# X15-ESC-CONTROLLER_-_Copy.net
KiCad netlist of a schematic drawn in EAGLE
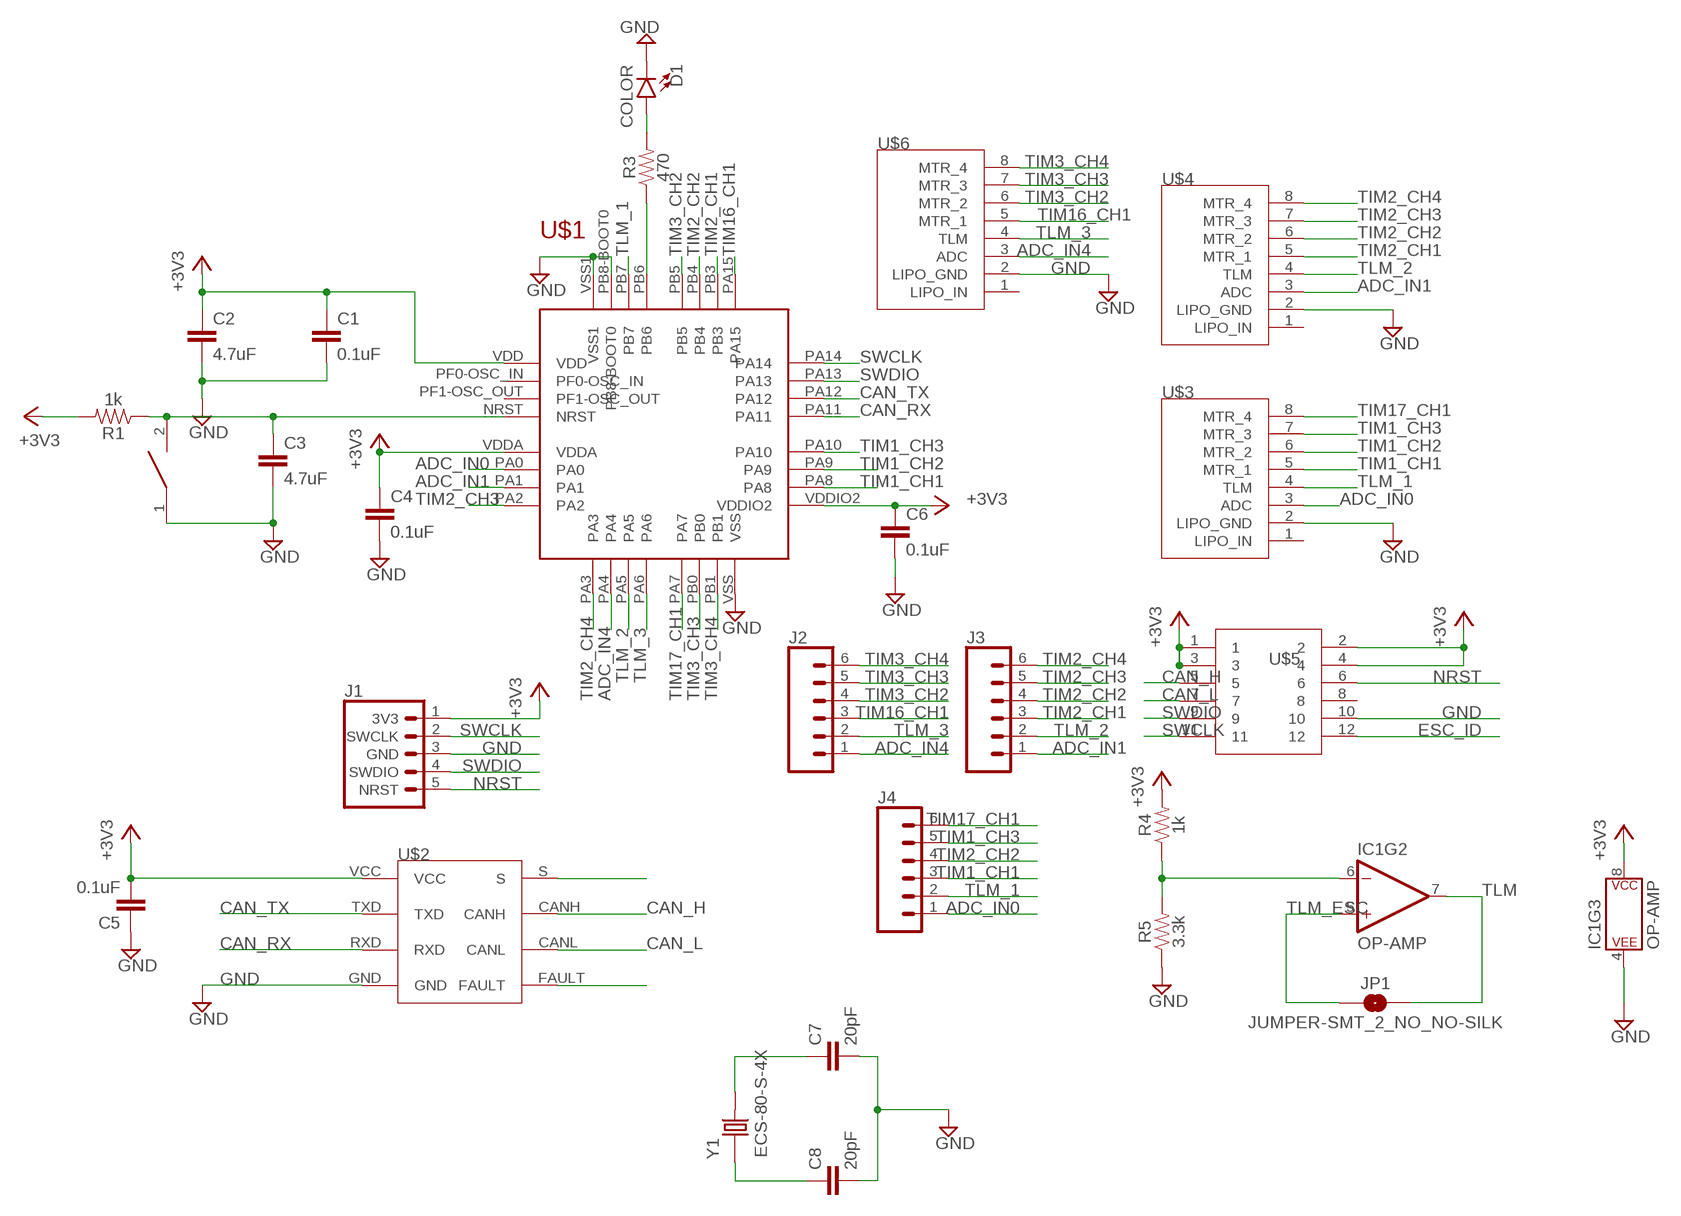
[diagram p0: schematic, sheet 1]

(export (version "E")
  (design (tool "Eeschema 10.0.6"))
  (components
    (comp (ref "C1")
      (value "0.1uF")
      (footprint "eagle-import:0603")
      (libsource (lib "eagle-import") (part "0.1UF-0603-25V-5%"))
    )
    (comp (ref "C2")
      (value "4.7uF")
      (footprint "eagle-import:0603")
      (libsource (lib "eagle-import") (part "4.7UF-0603-6.3V-(10%)"))
    )
    (comp (ref "C3")
      (value "4.7uF")
      (footprint "eagle-import:0603")
      (libsource (lib "eagle-import") (part "4.7UF-0603-6.3V-(10%)"))
    )
    (comp (ref "C4")
      (value "0.1uF")
      (footprint "eagle-import:0603")
      (libsource (lib "eagle-import") (part "0.1UF-0603-50V-10%-X7R-WE"))
    )
    (comp (ref "C5")
      (value "0.1uF")
      (footprint "eagle-import:0603")
      (libsource (lib "eagle-import") (part "0.1UF-0603-25V-(+80/-20%)"))
    )
    (comp (ref "C6")
      (value "0.1uF")
      (footprint "eagle-import:0603")
      (libsource (lib "eagle-import") (part "0.1UF-0603-25V-(+80/-20%)"))
    )
    (comp (ref "C7")
      (value "20pF")
      (footprint "eagle-import:0402-TIGHT")
      (libsource (lib "eagle-import") (part "20PF-0402T-50V-5%"))
    )
    (comp (ref "C8")
      (value "20pF")
      (footprint "eagle-import:0402-TIGHT")
      (libsource (lib "eagle-import") (part "20PF-0402T-50V-5%"))
    )
    (comp (ref "D1")
      (value "COLOR")
      (footprint "eagle-import:0805")
      (libsource (lib "eagle-import") (part "LED-0805"))
    )
    (comp (ref "IC1")
      (value "OP-AMP")
      (footprint "eagle-import:SO08")
      (libsource (lib "eagle-import") (part "OPAMP-DUALU"))
    )
    (comp (ref "J1")
      (value "3V3 -SWCLK-GND-SWDIO- NRST")
      (footprint "eagle-import:1X05")
      (libsource (lib "eagle-import") (part "SWD_CONN"))
    )
    (comp (ref "J2")
      (value "CONN_06NO_SILK_NO_POP")
      (footprint "eagle-import:1X06_NO_SILK")
      (libsource (lib "eagle-import") (part "CONN_06NO_SILK_NO_POP"))
    )
    (comp (ref "J3")
      (value "CONN_06NO_SILK_NO_POP")
      (footprint "eagle-import:1X06_NO_SILK")
      (libsource (lib "eagle-import") (part "CONN_06NO_SILK_NO_POP"))
    )
    (comp (ref "J4")
      (value "CONN_06NO_SILK_NO_POP")
      (footprint "eagle-import:1X06_NO_SILK")
      (libsource (lib "eagle-import") (part "CONN_06NO_SILK_NO_POP"))
    )
    (comp (ref "JP1")
      (value "JUMPER-SMT_2_NO_NO-SILK")
      (footprint "eagle-import:SMT-JUMPER_2_NO_NO-SILK")
      (libsource (lib "eagle-import") (part "JUMPER-SMT_2_NO_NO-SILK"))
    )
    (comp (ref "R1")
      (value "1k")
      (footprint "eagle-import:0603")
      (libsource (lib "eagle-import") (part "1KOHM-0603-1/10W-1%"))
    )
    (comp (ref "R3")
      (value "470")
      (footprint "eagle-import:0603")
      (libsource (lib "eagle-import") (part "10KOHM-0603-1/10W-1%"))
    )
    (comp (ref "R4")
      (value "1k")
      (footprint "eagle-import:0603")
      (libsource (lib "eagle-import") (part "1KOHM-0603-1/10W-1%"))
    )
    (comp (ref "R5")
      (value "3.3k")
      (footprint "eagle-import:0603")
      (libsource (lib "eagle-import") (part "1KOHM-0603-1/10W-1%"))
    )
    (comp (ref "U$1")
      (value "STM32F042K6T6")
      (footprint "eagle-import:STM32F042K6T6")
      (libsource (lib "eagle-import") (part "STM32F042K6T6"))
    )
    (comp (ref "U$2")
      (value "TCAN337D")
      (footprint "eagle-import:TCAN337D")
      (libsource (lib "eagle-import") (part "TCAN337D"))
    )
    (comp (ref "U$3")
      (value "JST_8_PIN")
      (footprint "eagle-import:JST_8_PIN")
      (libsource (lib "eagle-import") (part "JST_8_PIN"))
    )
    (comp (ref "U$4")
      (value "JST_8_PIN")
      (footprint "eagle-import:JST_8_PIN")
      (libsource (lib "eagle-import") (part "JST_8_PIN"))
    )
    (comp (ref "U$5")
      (value "BAKCPLANE_CONNECTOR")
      (footprint "eagle-import:BACKPLANE_CONNECTORS_BKP")
      (libsource (lib "eagle-import") (part "BAKCPLANE_CONNECTOR"))
    )
    (comp (ref "U$6")
      (value "JST_8_PIN")
      (footprint "eagle-import:JST_8_PIN")
      (libsource (lib "eagle-import") (part "JST_8_PIN"))
    )
    (comp (ref "U$7")
      (value "DISCRETECOMPONENTS_SWITCH")
      (footprint "eagle-import:DISCRETECOMPONENTS_SW_2512")
      (libsource (lib "eagle-import") (part "DISCRETECOMPONENTS_SWITCH"))
    )
    (comp (ref "Y1")
      (value "ECS-80-S-4X")
      (footprint "eagle-import:XTAL_ECS-80-S-4X")
      (fields (field (name "DIGI-KEY_PART_NUMBER") "X1057-ND") (field (name "MF") "ECS International"))
      (libsource (lib "eagle-import") (part "ECS-80-S-4X"))
    )
  )
  (nets
    (net (code "1") (name "+3V3") (class "Default")
      (node (ref "C1") (pin "1") (pinfunction "1_1") (pintype "passive"))
      (node (ref "C2") (pin "1") (pinfunction "1_1") (pintype "passive"))
      (node (ref "C4") (pin "1") (pinfunction "1_1") (pintype "passive"))
      (node (ref "C5") (pin "2") (pinfunction "2_2") (pintype "passive"))
      (node (ref "C6") (pin "1") (pinfunction "1_1") (pintype "passive"))
      (node (ref "IC1") (pin "8") (pinfunction "P$V+_8") (pintype "bidirectional"))
      (node (ref "J1") (pin "1") (pinfunction "3V3_1") (pintype "power_in"))
      (node (ref "R1") (pin "2") (pinfunction "2_2") (pintype "passive"))
      (node (ref "R4") (pin "2") (pinfunction "2_2") (pintype "passive"))
      (node (ref "U$1") (pin "VDD") (pinfunction "VDD_VDD") (pintype "bidirectional"))
      (node (ref "U$1") (pin "VDDA") (pinfunction "VDDA_VDDA") (pintype "bidirectional"))
      (node (ref "U$1") (pin "VDDIO2") (pinfunction "VDDIO2_VDDIO2") (pintype "bidirectional"))
      (node (ref "U$2") (pin "VCC") (pinfunction "VCC_VCC") (pintype "bidirectional"))
      (node (ref "U$5") (pin "1") (pinfunction "1_1") (pintype "bidirectional"))
      (node (ref "U$5") (pin "2") (pinfunction "2_2") (pintype "bidirectional"))
      (node (ref "U$5") (pin "3") (pinfunction "3_3") (pintype "bidirectional"))
      (node (ref "U$5") (pin "4") (pinfunction "4_4") (pintype "bidirectional"))
    )
    (net (code "2") (name "/ADC_IN0") (class "Default")
      (node (ref "J4") (pin "1") (pinfunction "1_1") (pintype "passive"))
      (node (ref "U$1") (pin "PA0") (pinfunction "PA0_PA0") (pintype "bidirectional"))
      (node (ref "U$3") (pin "3") (pinfunction "ADC_3") (pintype "bidirectional"))
    )
    (net (code "3") (name "/ADC_IN1") (class "Default")
      (node (ref "J3") (pin "1") (pinfunction "1_1") (pintype "passive"))
      (node (ref "U$1") (pin "PA1") (pinfunction "PA1_PA1") (pintype "bidirectional"))
      (node (ref "U$4") (pin "3") (pinfunction "ADC_3") (pintype "bidirectional"))
    )
    (net (code "4") (name "/ADC_IN4") (class "Default")
      (node (ref "J2") (pin "1") (pinfunction "1_1") (pintype "passive"))
      (node (ref "U$1") (pin "PA4") (pinfunction "PA4_PA4") (pintype "bidirectional"))
      (node (ref "U$6") (pin "3") (pinfunction "ADC_3") (pintype "bidirectional"))
    )
    (net (code "5") (name "/CAN_H") (class "Default")
      (node (ref "U$2") (pin "CANH") (pinfunction "CANH_CANH") (pintype "bidirectional"))
      (node (ref "U$5") (pin "5") (pinfunction "5_5") (pintype "bidirectional"))
    )
    (net (code "6") (name "/CAN_L") (class "Default")
      (node (ref "U$2") (pin "CANL") (pinfunction "CANL_CANL") (pintype "bidirectional"))
      (node (ref "U$5") (pin "7") (pinfunction "7_7") (pintype "bidirectional"))
    )
    (net (code "7") (name "/CAN_RX") (class "Default")
      (node (ref "U$1") (pin "PA11") (pinfunction "PA11_PA11") (pintype "bidirectional"))
      (node (ref "U$2") (pin "RXD") (pinfunction "RXD_RXD") (pintype "bidirectional"))
    )
    (net (code "8") (name "/CAN_TX") (class "Default")
      (node (ref "U$1") (pin "PA12") (pinfunction "PA12_PA12") (pintype "bidirectional"))
      (node (ref "U$2") (pin "TXD") (pinfunction "TXD_TXD") (pintype "bidirectional"))
    )
    (net (code "9") (name "/ESC_ID") (class "Default")
      (node (ref "U$5") (pin "12") (pinfunction "12_12") (pintype "bidirectional"))
    )
    (net (code "10") (name "/NRST") (class "Default")
      (node (ref "J1") (pin "5") (pinfunction "NRST_5") (pintype "open_collector"))
      (node (ref "U$5") (pin "6") (pinfunction "6_6") (pintype "bidirectional"))
    )
    (net (code "11") (name "/SWCLK") (class "Default")
      (node (ref "J1") (pin "2") (pinfunction "SWCLK_2") (pintype "input"))
      (node (ref "U$1") (pin "PA14") (pinfunction "PA14_PA14") (pintype "bidirectional"))
      (node (ref "U$5") (pin "11") (pinfunction "11_11") (pintype "bidirectional"))
    )
    (net (code "12") (name "/SWDIO") (class "Default")
      (node (ref "J1") (pin "4") (pinfunction "SWDIO_4") (pintype "bidirectional"))
      (node (ref "U$1") (pin "PA13") (pinfunction "PA13_PA13") (pintype "bidirectional"))
      (node (ref "U$5") (pin "9") (pinfunction "9_9") (pintype "bidirectional"))
    )
    (net (code "13") (name "/TIM1_CH1") (class "Default")
      (node (ref "J4") (pin "3") (pinfunction "3_3") (pintype "passive"))
      (node (ref "U$1") (pin "PA8") (pinfunction "PA8_PA8") (pintype "bidirectional"))
      (node (ref "U$3") (pin "5") (pinfunction "MTR_1_5") (pintype "bidirectional"))
    )
    (net (code "14") (name "/TIM1_CH2") (class "Default")
      (node (ref "U$1") (pin "PA9") (pinfunction "PA9_PA9") (pintype "bidirectional"))
      (node (ref "U$3") (pin "6") (pinfunction "MTR_2_6") (pintype "bidirectional"))
    )
    (net (code "15") (name "/TIM1_CH3") (class "Default")
      (node (ref "J4") (pin "5") (pinfunction "5_5") (pintype "passive"))
      (node (ref "U$1") (pin "PA10") (pinfunction "PA10_PA10") (pintype "bidirectional"))
      (node (ref "U$3") (pin "7") (pinfunction "MTR_3_7") (pintype "bidirectional"))
    )
    (net (code "16") (name "/TIM2_CH1") (class "Default")
      (node (ref "J3") (pin "3") (pinfunction "3_3") (pintype "passive"))
      (node (ref "U$1") (pin "PB3") (pinfunction "PB3_PB3") (pintype "bidirectional"))
      (node (ref "U$4") (pin "5") (pinfunction "MTR_1_5") (pintype "bidirectional"))
    )
    (net (code "17") (name "/TIM2_CH2") (class "Default")
      (node (ref "J3") (pin "4") (pinfunction "4_4") (pintype "passive"))
      (node (ref "J4") (pin "4") (pinfunction "4_4") (pintype "passive"))
      (node (ref "U$1") (pin "PB4") (pinfunction "PB4_PB4") (pintype "bidirectional"))
      (node (ref "U$4") (pin "6") (pinfunction "MTR_2_6") (pintype "bidirectional"))
    )
    (net (code "18") (name "/TIM2_CH3") (class "Default")
      (node (ref "J3") (pin "5") (pinfunction "5_5") (pintype "passive"))
      (node (ref "U$1") (pin "PA2") (pinfunction "PA2_PA2") (pintype "bidirectional"))
      (node (ref "U$4") (pin "7") (pinfunction "MTR_3_7") (pintype "bidirectional"))
    )
    (net (code "19") (name "/TIM2_CH4") (class "Default")
      (node (ref "J3") (pin "6") (pinfunction "6_6") (pintype "passive"))
      (node (ref "U$1") (pin "PA3") (pinfunction "PA3_PA3") (pintype "bidirectional"))
      (node (ref "U$4") (pin "8") (pinfunction "MTR_4_8") (pintype "bidirectional"))
    )
    (net (code "20") (name "/TIM3_CH2") (class "Default")
      (node (ref "J2") (pin "4") (pinfunction "4_4") (pintype "passive"))
      (node (ref "U$1") (pin "PB5") (pinfunction "PB5_PB5") (pintype "bidirectional"))
      (node (ref "U$6") (pin "6") (pinfunction "MTR_2_6") (pintype "bidirectional"))
    )
    (net (code "21") (name "/TIM3_CH3") (class "Default")
      (node (ref "J2") (pin "5") (pinfunction "5_5") (pintype "passive"))
      (node (ref "U$1") (pin "PB0") (pinfunction "PB0_PB0") (pintype "bidirectional"))
      (node (ref "U$6") (pin "7") (pinfunction "MTR_3_7") (pintype "bidirectional"))
    )
    (net (code "22") (name "/TIM3_CH4") (class "Default")
      (node (ref "J2") (pin "6") (pinfunction "6_6") (pintype "passive"))
      (node (ref "U$1") (pin "PB1") (pinfunction "PB1_PB1") (pintype "bidirectional"))
      (node (ref "U$6") (pin "8") (pinfunction "MTR_4_8") (pintype "bidirectional"))
    )
    (net (code "23") (name "/TIM16_CH1") (class "Default")
      (node (ref "J2") (pin "3") (pinfunction "3_3") (pintype "passive"))
      (node (ref "U$1") (pin "PA15") (pinfunction "PA15_PA15") (pintype "bidirectional"))
      (node (ref "U$6") (pin "5") (pinfunction "MTR_1_5") (pintype "bidirectional"))
    )
    (net (code "24") (name "/TIM17_CH1") (class "Default")
      (node (ref "J4") (pin "6") (pinfunction "6_6") (pintype "passive"))
      (node (ref "U$1") (pin "PA7") (pinfunction "PA7_PA7") (pintype "bidirectional"))
      (node (ref "U$3") (pin "8") (pinfunction "MTR_4_8") (pintype "bidirectional"))
    )
    (net (code "25") (name "/TLM") (class "Default")
      (node (ref "IC1") (pin "7") (pinfunction "OUT_7") (pintype "output"))
      (node (ref "JP1") (pin "2") (pinfunction "2_2") (pintype "passive"))
    )
    (net (code "26") (name "/TLM_1") (class "Default")
      (node (ref "J4") (pin "2") (pinfunction "2_2") (pintype "passive"))
      (node (ref "U$1") (pin "PB7") (pinfunction "PB7_PB7") (pintype "bidirectional"))
      (node (ref "U$3") (pin "4") (pinfunction "TLM_4") (pintype "bidirectional"))
    )
    (net (code "27") (name "/TLM_2") (class "Default")
      (node (ref "J3") (pin "2") (pinfunction "2_2") (pintype "passive"))
      (node (ref "U$1") (pin "PA5") (pinfunction "PA5_PA5") (pintype "bidirectional"))
      (node (ref "U$4") (pin "4") (pinfunction "TLM_4") (pintype "bidirectional"))
    )
    (net (code "28") (name "/TLM_3") (class "Default")
      (node (ref "J2") (pin "2") (pinfunction "2_2") (pintype "passive"))
      (node (ref "U$1") (pin "PA6") (pinfunction "PA6_PA6") (pintype "bidirectional"))
      (node (ref "U$6") (pin "4") (pinfunction "TLM_4") (pintype "bidirectional"))
    )
    (net (code "29") (name "/TLM_ESC") (class "Default")
      (node (ref "IC1") (pin "5") (pinfunction "+IN_5") (pintype "input"))
      (node (ref "JP1") (pin "1") (pinfunction "1_1") (pintype "passive"))
    )
    (net (code "30") (name "GND") (class "Default")
      (node (ref "C1") (pin "2") (pinfunction "2_2") (pintype "passive"))
      (node (ref "C2") (pin "2") (pinfunction "2_2") (pintype "passive"))
      (node (ref "C3") (pin "2") (pinfunction "2_2") (pintype "passive"))
      (node (ref "C4") (pin "2") (pinfunction "2_2") (pintype "passive"))
      (node (ref "C5") (pin "1") (pinfunction "1_1") (pintype "passive"))
      (node (ref "C6") (pin "2") (pinfunction "2_2") (pintype "passive"))
      (node (ref "C7") (pin "2") (pinfunction "2_2") (pintype "passive"))
      (node (ref "C8") (pin "2") (pinfunction "2_2") (pintype "passive"))
      (node (ref "D1") (pin "C") (pinfunction "C_C") (pintype "passive"))
      (node (ref "IC1") (pin "4") (pinfunction "P$V-_4") (pintype "bidirectional"))
      (node (ref "J1") (pin "3") (pinfunction "GND_3") (pintype "power_in"))
      (node (ref "R5") (pin "1") (pinfunction "1_1") (pintype "passive"))
      (node (ref "U$1") (pin "PB8-BOOT0") (pinfunction "PB8-BOOT0_PB8-BOOT0") (pintype "bidirectional"))
      (node (ref "U$1") (pin "VSS") (pinfunction "VSS_VSS") (pintype "bidirectional"))
      (node (ref "U$1") (pin "VSS1") (pinfunction "VSS1_VSS1") (pintype "bidirectional"))
      (node (ref "U$2") (pin "GND") (pinfunction "GND_GND") (pintype "bidirectional"))
      (node (ref "U$3") (pin "2") (pinfunction "LIPO_GND_2") (pintype "bidirectional"))
      (node (ref "U$4") (pin "2") (pinfunction "LIPO_GND_2") (pintype "bidirectional"))
      (node (ref "U$5") (pin "10") (pinfunction "10_10") (pintype "bidirectional"))
      (node (ref "U$6") (pin "2") (pinfunction "LIPO_GND_2") (pintype "bidirectional"))
      (node (ref "U$7") (pin "1") (pinfunction "P$1_1") (pintype "bidirectional"))
    )
    (net (code "31") (name "Net-(C7-Pad1)") (class "Default")
      (node (ref "C7") (pin "1") (pinfunction "1_1") (pintype "passive"))
      (node (ref "Y1") (pin "2") (pinfunction "2_2") (pintype "passive"))
    )
    (net (code "32") (name "Net-(C8-Pad1)") (class "Default")
      (node (ref "C8") (pin "1") (pinfunction "1_1") (pintype "passive"))
      (node (ref "Y1") (pin "1") (pinfunction "1_1") (pintype "passive"))
    )
    (net (code "33") (name "Net-(D1-PadA)") (class "Default")
      (node (ref "D1") (pin "A") (pinfunction "A_A") (pintype "passive"))
      (node (ref "R3") (pin "2") (pinfunction "2_2") (pintype "passive"))
    )
    (net (code "34") (name "Net-(IC1B--IN)") (class "Default")
      (node (ref "IC1") (pin "6") (pinfunction "-IN_6") (pintype "input"))
      (node (ref "R4") (pin "1") (pinfunction "1_1") (pintype "passive"))
      (node (ref "R5") (pin "2") (pinfunction "2_2") (pintype "passive"))
    )
    (net (code "35") (name "Net-(R3-Pad1)") (class "Default")
      (node (ref "R3") (pin "1") (pinfunction "1_1") (pintype "passive"))
      (node (ref "U$1") (pin "PB6") (pinfunction "PB6_PB6") (pintype "bidirectional"))
    )
    (net (code "36") (name "Net-(U$7-P$2)") (class "Default")
      (node (ref "C3") (pin "1") (pinfunction "1_1") (pintype "passive"))
      (node (ref "R1") (pin "1") (pinfunction "1_1") (pintype "passive"))
      (node (ref "U$1") (pin "NRST") (pinfunction "NRST_NRST") (pintype "bidirectional"))
      (node (ref "U$7") (pin "2") (pinfunction "P$2_2") (pintype "bidirectional"))
    )
    (net (code "37") (name "unconnected-(U$1-PadPF0-OSC_IN)") (class "Default")
      (node (ref "U$1") (pin "PF0-OSC_IN") (pinfunction "PF0-OSC_IN_PF0-OSC_IN") (pintype "bidirectional"))
    )
    (net (code "38") (name "unconnected-(U$1-PadPF1-OSC_OUT)") (class "Default")
      (node (ref "U$1") (pin "PF1-OSC_OUT") (pinfunction "PF1-OSC_OUT_PF1-OSC_OUT") (pintype "bidirectional"))
    )
    (net (code "39") (name "unconnected-(U$2-PadFAULT)") (class "Default")
      (node (ref "U$2") (pin "FAULT") (pinfunction "FAULT_FAULT") (pintype "bidirectional"))
    )
    (net (code "40") (name "unconnected-(U$2-PadS)") (class "Default")
      (node (ref "U$2") (pin "S") (pinfunction "S_S") (pintype "bidirectional"))
    )
    (net (code "41") (name "unconnected-(U$3-LIPO_IN-Pad1)") (class "Default")
      (node (ref "U$3") (pin "1") (pinfunction "LIPO_IN_1") (pintype "bidirectional"))
    )
    (net (code "42") (name "unconnected-(U$4-LIPO_IN-Pad1)") (class "Default")
      (node (ref "U$4") (pin "1") (pinfunction "LIPO_IN_1") (pintype "bidirectional"))
    )
    (net (code "43") (name "unconnected-(U$5-Pad8)") (class "Default")
      (node (ref "U$5") (pin "8") (pinfunction "8_8") (pintype "bidirectional"))
    )
    (net (code "44") (name "unconnected-(U$6-LIPO_IN-Pad1)") (class "Default")
      (node (ref "U$6") (pin "1") (pinfunction "LIPO_IN_1") (pintype "bidirectional"))
    )
  )
)
